# BMS_Rev2_power.net
KiCad netlist of a schematic drawn in EAGLE
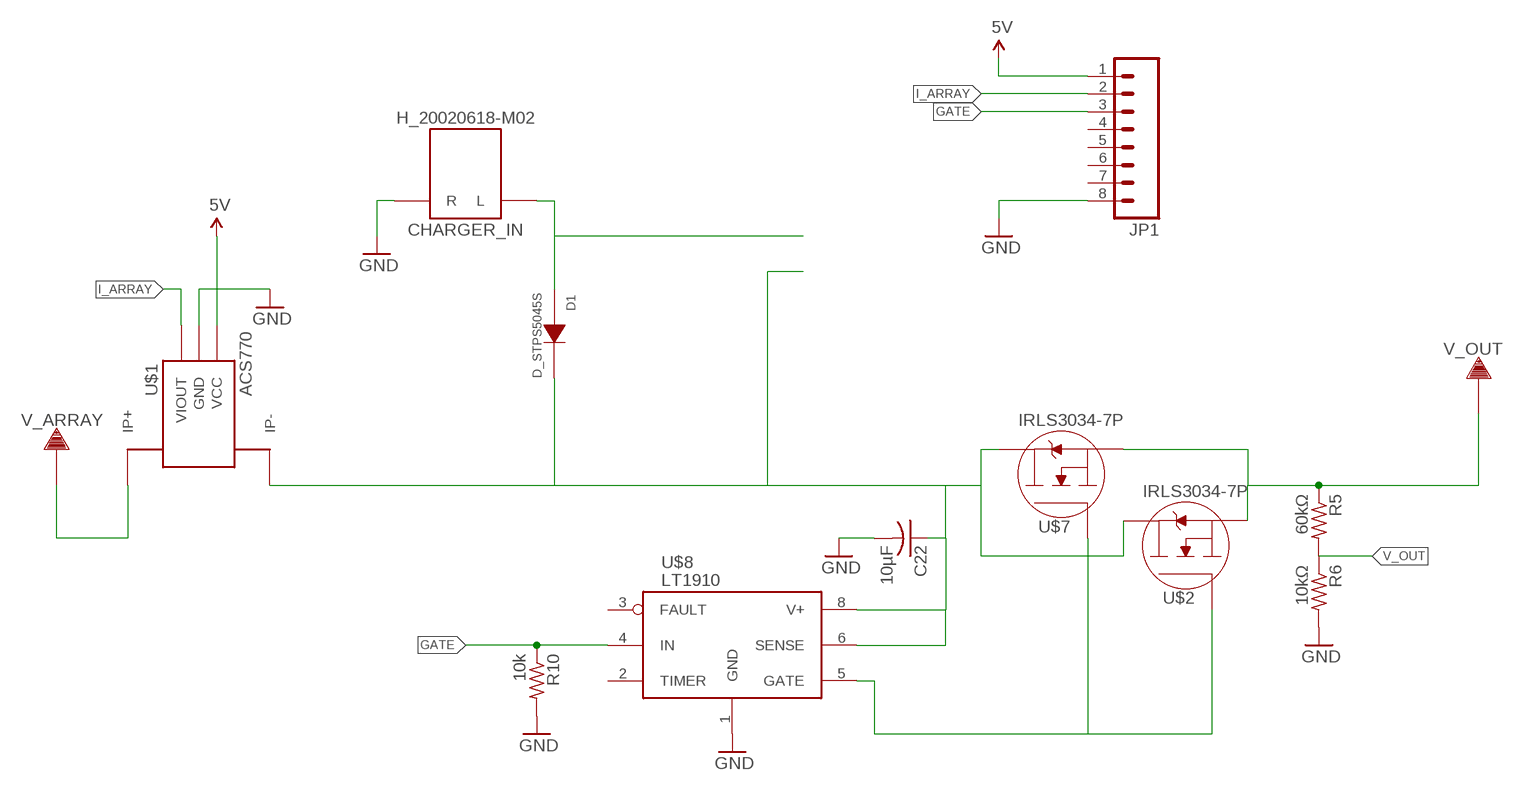
[diagram p0: schematic, sheet 1]

(export (version "E")
  (design (tool "Eeschema 10.0.6"))
  (components
    (comp (ref "C22")
      (value "10µF")
      (footprint "eagle-import:C1206")
      (libsource (lib "eagle-import") (part "C-USC1206"))
    )
    (comp (ref "CHARGER_IN")
      (value "H_20020618-M02")
      (footprint "eagle-import:20020618-M02")
      (libsource (lib "eagle-import") (part "H_20020618-M02"))
    )
    (comp (ref "D1")
      (value "D_STPS5045S")
      (footprint "eagle-import:D2PACK")
      (libsource (lib "eagle-import") (part "D_STPS5045S"))
    )
    (comp (ref "JP1")
      (value "M08BM08B-SRSS-TB")
      (footprint "eagle-import:BM08B-SRSS-TB")
      (libsource (lib "eagle-import") (part "M08BM08B-SRSS-TB"))
    )
    (comp (ref "R5")
      (value "60kΩ")
      (footprint "eagle-import:R1206")
      (libsource (lib "eagle-import") (part "R-US_R1206"))
    )
    (comp (ref "R6")
      (value "10kΩ")
      (footprint "eagle-import:R1206")
      (libsource (lib "eagle-import") (part "R-US_R1206"))
    )
    (comp (ref "R10")
      (value "10k")
      (footprint "eagle-import:R1206")
      (libsource (lib "eagle-import") (part "R-US_R1206"))
    )
    (comp (ref "U$1")
      (value "ACS770")
      (footprint "eagle-import:PFF_LEADFORM")
      (libsource (lib "eagle-import") (part "ACS770"))
    )
    (comp (ref "U$2")
      (value "IRLS3034-7P")
      (footprint "eagle-import:D2PAK-7")
      (libsource (lib "eagle-import") (part "IRLS3034-7P"))
    )
    (comp (ref "U$7")
      (value "IRLS3034-7P")
      (footprint "eagle-import:D2PAK-7")
      (libsource (lib "eagle-import") (part "IRLS3034-7P"))
    )
    (comp (ref "U$8")
      (value "LT1910")
      (footprint "eagle-import:SO8")
      (libsource (lib "eagle-import") (part "LT1910"))
    )
    (comp (ref "V_ARRAY")
      (value "TERMINAL_HOLE")
      (footprint "eagle-import:LARGE_TERMINAL_HOLE")
      (libsource (lib "eagle-import") (part "TERMINAL_HOLE"))
    )
    (comp (ref "V_OUT")
      (value "TERMINAL_HOLE")
      (footprint "eagle-import:LARGE_TERMINAL_HOLE")
      (libsource (lib "eagle-import") (part "TERMINAL_HOLE"))
    )
  )
  (nets
    (net (code "1") (name "5V") (class "Default")
      (node (ref "JP1") (pin "1") (pinfunction "1_1") (pintype "passive"))
      (node (ref "U$1") (pin "1") (pinfunction "VCC_1") (pintype "bidirectional"))
    )
    (net (code "2") (name "GATE") (class "Default")
      (node (ref "JP1") (pin "3") (pinfunction "3_3") (pintype "passive"))
      (node (ref "R10") (pin "1") (pinfunction "1_1") (pintype "passive"))
      (node (ref "U$8") (pin "4") (pinfunction "IN_4") (pintype "bidirectional"))
    )
    (net (code "3") (name "GND") (class "Default")
      (node (ref "C22") (pin "2") (pinfunction "2_2") (pintype "passive"))
      (node (ref "CHARGER_IN") (pin "R1") (pinfunction "R_R1") (pintype "bidirectional"))
      (node (ref "CHARGER_IN") (pin "R2") (pinfunction "R_R2") (pintype "bidirectional"))
      (node (ref "JP1") (pin "8") (pinfunction "8_8") (pintype "passive"))
      (node (ref "R10") (pin "2") (pinfunction "2_2") (pintype "passive"))
      (node (ref "R6") (pin "2") (pinfunction "2_2") (pintype "passive"))
      (node (ref "U$1") (pin "2") (pinfunction "GND_2") (pintype "bidirectional"))
      (node (ref "U$8") (pin "1") (pinfunction "GND_1") (pintype "bidirectional"))
    )
    (net (code "4") (name "I_ARRAY") (class "Default")
      (node (ref "JP1") (pin "2") (pinfunction "2_2") (pintype "passive"))
      (node (ref "U$1") (pin "3") (pinfunction "VIOUT_3") (pintype "bidirectional"))
    )
    (net (code "5") (name "Net-(CHARGER_IN-L-PadL1)") (class "Default")
      (node (ref "CHARGER_IN") (pin "L1") (pinfunction "L_L1") (pintype "bidirectional"))
      (node (ref "CHARGER_IN") (pin "L2") (pinfunction "L_L2") (pintype "bidirectional"))
      (node (ref "D1") (pin "1") (pinfunction "A_1") (pintype "bidirectional"))
      (node (ref "D1") (pin "2") (pinfunction "A_2") (pintype "bidirectional"))
    )
    (net (code "6") (name "Net-(D1-K)") (class "Default")
      (node (ref "C22") (pin "1") (pinfunction "1_1") (pintype "passive"))
      (node (ref "D1") (pin "TAB") (pinfunction "K_TAB") (pintype "bidirectional"))
      (node (ref "U$1") (pin "5_1") (pinfunction "IP-_5_1") (pintype "bidirectional"))
      (node (ref "U$1") (pin "5_10") (pinfunction "IP-_5_10") (pintype "bidirectional"))
      (node (ref "U$1") (pin "5_11") (pinfunction "IP-_5_11") (pintype "bidirectional"))
      (node (ref "U$1") (pin "5_12") (pinfunction "IP-_5_12") (pintype "bidirectional"))
      (node (ref "U$1") (pin "5_13") (pinfunction "IP-_5_13") (pintype "bidirectional"))
      (node (ref "U$1") (pin "5_14") (pinfunction "IP-_5_14") (pintype "bidirectional"))
      (node (ref "U$1") (pin "5_15") (pinfunction "IP-_5_15") (pintype "bidirectional"))
      (node (ref "U$1") (pin "5_16") (pinfunction "IP-_5_16") (pintype "bidirectional"))
      (node (ref "U$1") (pin "5_2") (pinfunction "IP-_5_2") (pintype "bidirectional"))
      (node (ref "U$1") (pin "5_3") (pinfunction "IP-_5_3") (pintype "bidirectional"))
      (node (ref "U$1") (pin "5_4") (pinfunction "IP-_5_4") (pintype "bidirectional"))
      (node (ref "U$1") (pin "5_5") (pinfunction "IP-_5_5") (pintype "bidirectional"))
      (node (ref "U$1") (pin "5_6") (pinfunction "IP-_5_6") (pintype "bidirectional"))
      (node (ref "U$1") (pin "5_7") (pinfunction "IP-_5_7") (pintype "bidirectional"))
      (node (ref "U$1") (pin "5_8") (pinfunction "IP-_5_8") (pintype "bidirectional"))
      (node (ref "U$1") (pin "5_9") (pinfunction "IP-_5_9") (pintype "bidirectional"))
      (node (ref "U$1") (pin "5_B") (pinfunction "IP-_5_B") (pintype "bidirectional"))
      (node (ref "U$1") (pin "5_T") (pinfunction "IP-_5_T") (pintype "bidirectional"))
      (node (ref "U$2") (pin "PAD") (pinfunction "DRAIN_PAD") (pintype "bidirectional"))
      (node (ref "U$7") (pin "PAD") (pinfunction "DRAIN_PAD") (pintype "bidirectional"))
      (node (ref "U$8") (pin "6") (pinfunction "SENSE_6") (pintype "bidirectional"))
      (node (ref "U$8") (pin "8") (pinfunction "V+_8") (pintype "bidirectional"))
    )
    (net (code "7") (name "Net-(R5-Pad1)") (class "Default")
      (node (ref "R5") (pin "1") (pinfunction "1_1") (pintype "passive"))
      (node (ref "U$2") (pin "2") (pinfunction "SOURCE_2") (pintype "bidirectional"))
      (node (ref "U$2") (pin "3") (pinfunction "SOURCE_3") (pintype "bidirectional"))
      (node (ref "U$2") (pin "4") (pinfunction "SOURCE_4") (pintype "bidirectional"))
      (node (ref "U$2") (pin "5") (pinfunction "SOURCE_5") (pintype "bidirectional"))
      (node (ref "U$2") (pin "6") (pinfunction "SOURCE_6") (pintype "bidirectional"))
      (node (ref "U$7") (pin "2") (pinfunction "SOURCE_2") (pintype "bidirectional"))
      (node (ref "U$7") (pin "3") (pinfunction "SOURCE_3") (pintype "bidirectional"))
      (node (ref "U$7") (pin "4") (pinfunction "SOURCE_4") (pintype "bidirectional"))
      (node (ref "U$7") (pin "5") (pinfunction "SOURCE_5") (pintype "bidirectional"))
      (node (ref "U$7") (pin "6") (pinfunction "SOURCE_6") (pintype "bidirectional"))
      (node (ref "V_OUT") (pin "P$1") (pinfunction "P$1_P$1") (pintype "bidirectional"))
    )
    (net (code "8") (name "Net-(U$1-IP+-Pad4_1)") (class "Default")
      (node (ref "U$1") (pin "4_1") (pinfunction "IP+_4_1") (pintype "bidirectional"))
      (node (ref "U$1") (pin "4_10") (pinfunction "IP+_4_10") (pintype "bidirectional"))
      (node (ref "U$1") (pin "4_11") (pinfunction "IP+_4_11") (pintype "bidirectional"))
      (node (ref "U$1") (pin "4_12") (pinfunction "IP+_4_12") (pintype "bidirectional"))
      (node (ref "U$1") (pin "4_13") (pinfunction "IP+_4_13") (pintype "bidirectional"))
      (node (ref "U$1") (pin "4_14") (pinfunction "IP+_4_14") (pintype "bidirectional"))
      (node (ref "U$1") (pin "4_15") (pinfunction "IP+_4_15") (pintype "bidirectional"))
      (node (ref "U$1") (pin "4_16") (pinfunction "IP+_4_16") (pintype "bidirectional"))
      (node (ref "U$1") (pin "4_2") (pinfunction "IP+_4_2") (pintype "bidirectional"))
      (node (ref "U$1") (pin "4_3") (pinfunction "IP+_4_3") (pintype "bidirectional"))
      (node (ref "U$1") (pin "4_4") (pinfunction "IP+_4_4") (pintype "bidirectional"))
      (node (ref "U$1") (pin "4_5") (pinfunction "IP+_4_5") (pintype "bidirectional"))
      (node (ref "U$1") (pin "4_6") (pinfunction "IP+_4_6") (pintype "bidirectional"))
      (node (ref "U$1") (pin "4_7") (pinfunction "IP+_4_7") (pintype "bidirectional"))
      (node (ref "U$1") (pin "4_8") (pinfunction "IP+_4_8") (pintype "bidirectional"))
      (node (ref "U$1") (pin "4_9") (pinfunction "IP+_4_9") (pintype "bidirectional"))
      (node (ref "U$1") (pin "4_B") (pinfunction "IP+_4_B") (pintype "bidirectional"))
      (node (ref "U$1") (pin "4_T") (pinfunction "IP+_4_T") (pintype "bidirectional"))
      (node (ref "V_ARRAY") (pin "P$1") (pinfunction "P$1_P$1") (pintype "bidirectional"))
    )
    (net (code "9") (name "Net-(U$2-GATE)") (class "Default")
      (node (ref "U$2") (pin "1") (pinfunction "GATE_1") (pintype "bidirectional"))
      (node (ref "U$7") (pin "1") (pinfunction "GATE_1") (pintype "bidirectional"))
      (node (ref "U$8") (pin "5") (pinfunction "GATE_5") (pintype "bidirectional"))
    )
    (net (code "10") (name "V_OUT") (class "Default")
      (node (ref "R5") (pin "2") (pinfunction "2_2") (pintype "passive"))
      (node (ref "R6") (pin "1") (pinfunction "1_1") (pintype "passive"))
    )
    (net (code "11") (name "unconnected-(JP1-Pad4)") (class "Default")
      (node (ref "JP1") (pin "4") (pinfunction "4_4") (pintype "passive"))
    )
    (net (code "12") (name "unconnected-(JP1-Pad5)") (class "Default")
      (node (ref "JP1") (pin "5") (pinfunction "5_5") (pintype "passive"))
    )
    (net (code "13") (name "unconnected-(JP1-Pad6)") (class "Default")
      (node (ref "JP1") (pin "6") (pinfunction "6_6") (pintype "passive"))
    )
    (net (code "14") (name "unconnected-(JP1-Pad7)") (class "Default")
      (node (ref "JP1") (pin "7") (pinfunction "7_7") (pintype "passive"))
    )
    (net (code "15") (name "unconnected-(U$8-FAULT-Pad3)") (class "Default")
      (node (ref "U$8") (pin "3") (pinfunction "FAULT_3") (pintype "bidirectional"))
    )
    (net (code "16") (name "unconnected-(U$8-TIMER-Pad2)") (class "Default")
      (node (ref "U$8") (pin "2") (pinfunction "TIMER_2") (pintype "bidirectional"))
    )
  )
)
